# xen_matrix_controls_6x6.net
KiCad netlist of a schematic drawn in EAGLE
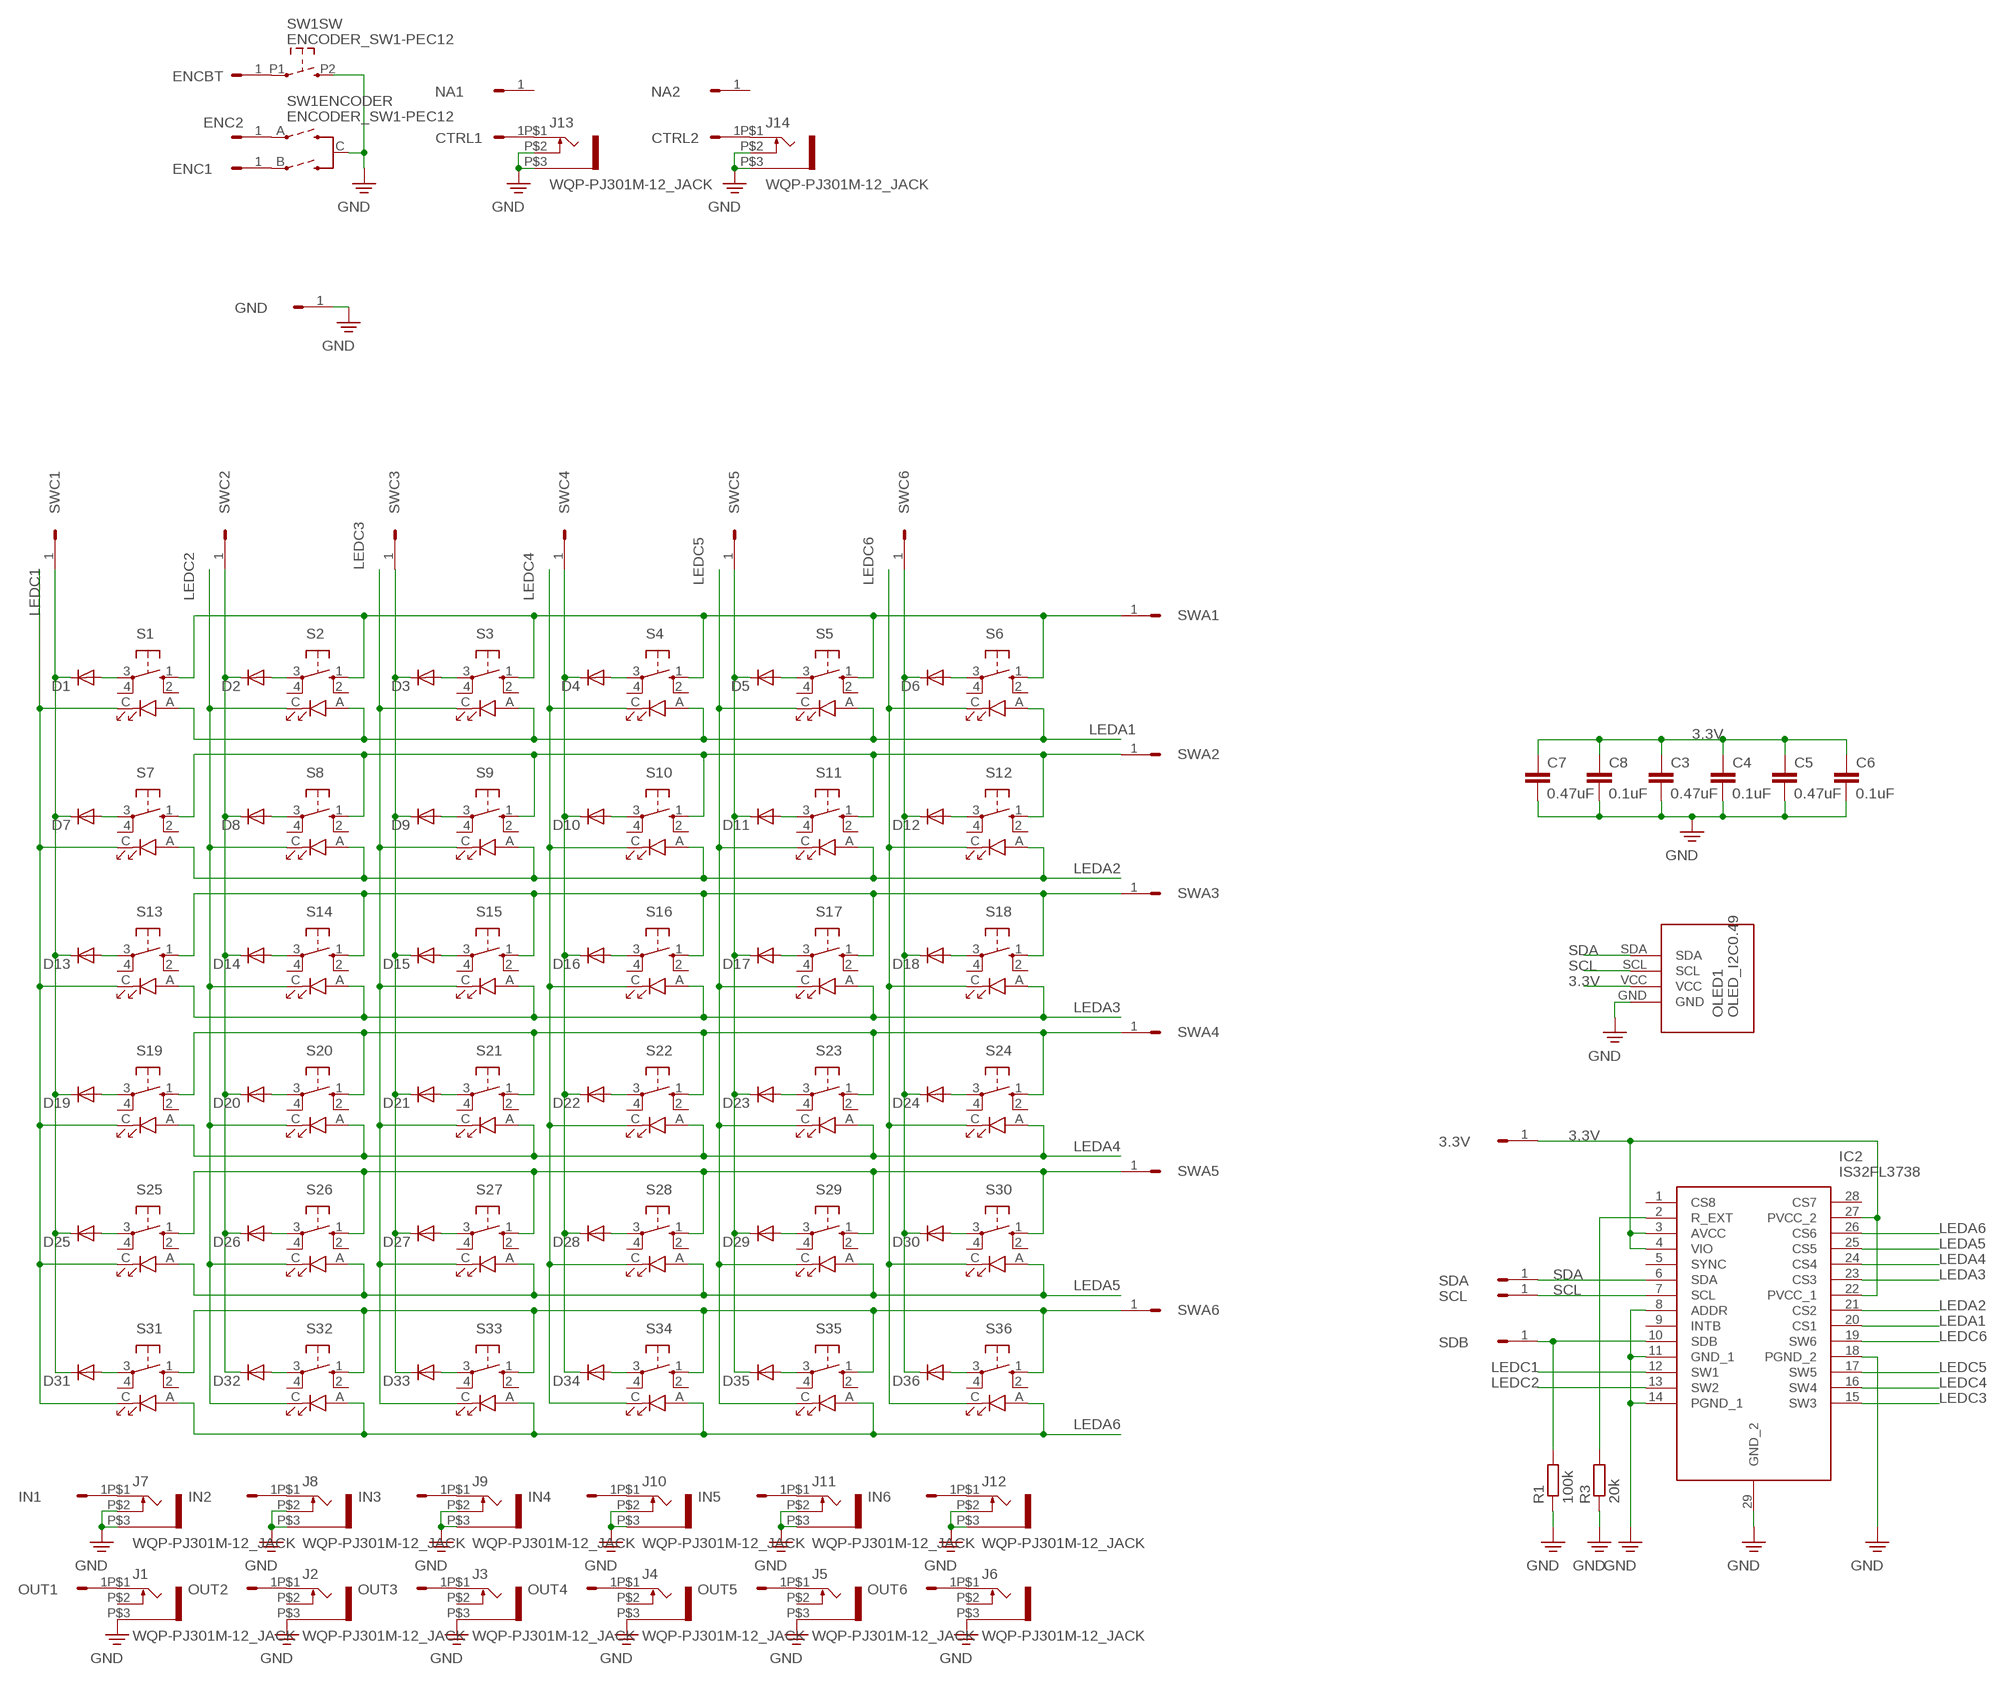
[diagram p0: schematic, sheet 1]

(export (version "E")
  (design (tool "Eeschema 10.0.6"))
  (components
    (comp (ref "3.3V")
      (value "HEADER/MALE/01")
      (footprint "eagle-import:HEADER_MALE_01")
      (fields (field (name "SPICEPREFIX") "X"))
      (libsource (lib "eagle-import") (part "HEADER/MALE/01"))
    )
    (comp (ref "C3")
      (value "0.47uF")
      (footprint "eagle-import:C0603")
      (libsource (lib "eagle-import") (part "CAPACITORC0603"))
    )
    (comp (ref "C4")
      (value "0.1uF")
      (footprint "eagle-import:C0603")
      (libsource (lib "eagle-import") (part "CAPACITORC0603"))
    )
    (comp (ref "C5")
      (value "0.47uF")
      (footprint "eagle-import:C0603")
      (libsource (lib "eagle-import") (part "CAPACITORC0603"))
    )
    (comp (ref "C6")
      (value "0.1uF")
      (footprint "eagle-import:C0603")
      (libsource (lib "eagle-import") (part "CAPACITORC0603"))
    )
    (comp (ref "C7")
      (value "0.47uF")
      (footprint "eagle-import:C0603")
      (libsource (lib "eagle-import") (part "CAPACITORC0603"))
    )
    (comp (ref "C8")
      (value "0.1uF")
      (footprint "eagle-import:C0603")
      (libsource (lib "eagle-import") (part "CAPACITORC0603"))
    )
    (comp (ref "CTRL1")
      (value "HEADER/MALE/01")
      (footprint "eagle-import:HEADER_MALE_01")
      (fields (field (name "SPICEPREFIX") "X"))
      (libsource (lib "eagle-import") (part "HEADER/MALE/01"))
    )
    (comp (ref "CTRL2")
      (value "HEADER/MALE/01")
      (footprint "eagle-import:HEADER_MALE_01")
      (fields (field (name "SPICEPREFIX") "X"))
      (libsource (lib "eagle-import") (part "HEADER/MALE/01"))
    )
    (comp (ref "D1")
      (value "1N4148SOD-123")
      (footprint "eagle-import:SOD-123")
      (libsource (lib "eagle-import") (part "1N4148SOD-123"))
    )
    (comp (ref "D2")
      (value "1N4148SOD-123")
      (footprint "eagle-import:SOD-123")
      (libsource (lib "eagle-import") (part "1N4148SOD-123"))
    )
    (comp (ref "D3")
      (value "1N4148SOD-123")
      (footprint "eagle-import:SOD-123")
      (libsource (lib "eagle-import") (part "1N4148SOD-123"))
    )
    (comp (ref "D4")
      (value "1N4148SOD-123")
      (footprint "eagle-import:SOD-123")
      (libsource (lib "eagle-import") (part "1N4148SOD-123"))
    )
    (comp (ref "D5")
      (value "1N4148SOD-123")
      (footprint "eagle-import:SOD-123")
      (libsource (lib "eagle-import") (part "1N4148SOD-123"))
    )
    (comp (ref "D6")
      (value "1N4148SOD-123")
      (footprint "eagle-import:SOD-123")
      (libsource (lib "eagle-import") (part "1N4148SOD-123"))
    )
    (comp (ref "D7")
      (value "1N4148SOD-123")
      (footprint "eagle-import:SOD-123")
      (libsource (lib "eagle-import") (part "1N4148SOD-123"))
    )
    (comp (ref "D8")
      (value "1N4148SOD-123")
      (footprint "eagle-import:SOD-123")
      (libsource (lib "eagle-import") (part "1N4148SOD-123"))
    )
    (comp (ref "D9")
      (value "1N4148SOD-123")
      (footprint "eagle-import:SOD-123")
      (libsource (lib "eagle-import") (part "1N4148SOD-123"))
    )
    (comp (ref "D10")
      (value "1N4148SOD-123")
      (footprint "eagle-import:SOD-123")
      (libsource (lib "eagle-import") (part "1N4148SOD-123"))
    )
    (comp (ref "D11")
      (value "1N4148SOD-123")
      (footprint "eagle-import:SOD-123")
      (libsource (lib "eagle-import") (part "1N4148SOD-123"))
    )
    (comp (ref "D12")
      (value "1N4148SOD-123")
      (footprint "eagle-import:SOD-123")
      (libsource (lib "eagle-import") (part "1N4148SOD-123"))
    )
    (comp (ref "D13")
      (value "1N4148SOD-123")
      (footprint "eagle-import:SOD-123")
      (libsource (lib "eagle-import") (part "1N4148SOD-123"))
    )
    (comp (ref "D14")
      (value "1N4148SOD-123")
      (footprint "eagle-import:SOD-123")
      (libsource (lib "eagle-import") (part "1N4148SOD-123"))
    )
    (comp (ref "D15")
      (value "1N4148SOD-123")
      (footprint "eagle-import:SOD-123")
      (libsource (lib "eagle-import") (part "1N4148SOD-123"))
    )
    (comp (ref "D16")
      (value "1N4148SOD-123")
      (footprint "eagle-import:SOD-123")
      (libsource (lib "eagle-import") (part "1N4148SOD-123"))
    )
    (comp (ref "D17")
      (value "1N4148SOD-123")
      (footprint "eagle-import:SOD-123")
      (libsource (lib "eagle-import") (part "1N4148SOD-123"))
    )
    (comp (ref "D18")
      (value "1N4148SOD-123")
      (footprint "eagle-import:SOD-123")
      (libsource (lib "eagle-import") (part "1N4148SOD-123"))
    )
    (comp (ref "D19")
      (value "1N4148SOD-123")
      (footprint "eagle-import:SOD-123")
      (libsource (lib "eagle-import") (part "1N4148SOD-123"))
    )
    (comp (ref "D20")
      (value "1N4148SOD-123")
      (footprint "eagle-import:SOD-123")
      (libsource (lib "eagle-import") (part "1N4148SOD-123"))
    )
    (comp (ref "D21")
      (value "1N4148SOD-123")
      (footprint "eagle-import:SOD-123")
      (libsource (lib "eagle-import") (part "1N4148SOD-123"))
    )
    (comp (ref "D22")
      (value "1N4148SOD-123")
      (footprint "eagle-import:SOD-123")
      (libsource (lib "eagle-import") (part "1N4148SOD-123"))
    )
    (comp (ref "D23")
      (value "1N4148SOD-123")
      (footprint "eagle-import:SOD-123")
      (libsource (lib "eagle-import") (part "1N4148SOD-123"))
    )
    (comp (ref "D24")
      (value "1N4148SOD-123")
      (footprint "eagle-import:SOD-123")
      (libsource (lib "eagle-import") (part "1N4148SOD-123"))
    )
    (comp (ref "D25")
      (value "1N4148SOD-123")
      (footprint "eagle-import:SOD-123")
      (libsource (lib "eagle-import") (part "1N4148SOD-123"))
    )
    (comp (ref "D26")
      (value "1N4148SOD-123")
      (footprint "eagle-import:SOD-123")
      (libsource (lib "eagle-import") (part "1N4148SOD-123"))
    )
    (comp (ref "D27")
      (value "1N4148SOD-123")
      (footprint "eagle-import:SOD-123")
      (libsource (lib "eagle-import") (part "1N4148SOD-123"))
    )
    (comp (ref "D28")
      (value "1N4148SOD-123")
      (footprint "eagle-import:SOD-123")
      (libsource (lib "eagle-import") (part "1N4148SOD-123"))
    )
    (comp (ref "D29")
      (value "1N4148SOD-123")
      (footprint "eagle-import:SOD-123")
      (libsource (lib "eagle-import") (part "1N4148SOD-123"))
    )
    (comp (ref "D30")
      (value "1N4148SOD-123")
      (footprint "eagle-import:SOD-123")
      (libsource (lib "eagle-import") (part "1N4148SOD-123"))
    )
    (comp (ref "D31")
      (value "1N4148SOD-123")
      (footprint "eagle-import:SOD-123")
      (libsource (lib "eagle-import") (part "1N4148SOD-123"))
    )
    (comp (ref "D32")
      (value "1N4148SOD-123")
      (footprint "eagle-import:SOD-123")
      (libsource (lib "eagle-import") (part "1N4148SOD-123"))
    )
    (comp (ref "D33")
      (value "1N4148SOD-123")
      (footprint "eagle-import:SOD-123")
      (libsource (lib "eagle-import") (part "1N4148SOD-123"))
    )
    (comp (ref "D34")
      (value "1N4148SOD-123")
      (footprint "eagle-import:SOD-123")
      (libsource (lib "eagle-import") (part "1N4148SOD-123"))
    )
    (comp (ref "D35")
      (value "1N4148SOD-123")
      (footprint "eagle-import:SOD-123")
      (libsource (lib "eagle-import") (part "1N4148SOD-123"))
    )
    (comp (ref "D36")
      (value "1N4148SOD-123")
      (footprint "eagle-import:SOD-123")
      (libsource (lib "eagle-import") (part "1N4148SOD-123"))
    )
    (comp (ref "ENC1")
      (value "HEADER/MALE/01")
      (footprint "eagle-import:HEADER_MALE_01")
      (fields (field (name "SPICEPREFIX") "X"))
      (libsource (lib "eagle-import") (part "HEADER/MALE/01"))
    )
    (comp (ref "ENC2")
      (value "HEADER/MALE/01")
      (footprint "eagle-import:HEADER_MALE_01")
      (fields (field (name "SPICEPREFIX") "X"))
      (libsource (lib "eagle-import") (part "HEADER/MALE/01"))
    )
    (comp (ref "ENCBT")
      (value "HEADER/MALE/01")
      (footprint "eagle-import:HEADER_MALE_01")
      (fields (field (name "SPICEPREFIX") "X"))
      (libsource (lib "eagle-import") (part "HEADER/MALE/01"))
    )
    (comp (ref "GND")
      (value "HEADER/MALE/01")
      (footprint "eagle-import:HEADER_MALE_01")
      (fields (field (name "SPICEPREFIX") "X"))
      (libsource (lib "eagle-import") (part "HEADER/MALE/01"))
    )
    (comp (ref "IC2")
      (value "IS32FL3738")
      (footprint "eagle-import:TSSOP29")
      (fields (field (name "MANUFACTURER_PART_NUMBER") "IS32FL3738-ZLA3-TR"))
      (libsource (lib "eagle-import") (part "IS32FL3738"))
    )
    (comp (ref "IN1")
      (value "HEADER/MALE/01")
      (footprint "eagle-import:HEADER_MALE_01")
      (fields (field (name "SPICEPREFIX") "X"))
      (libsource (lib "eagle-import") (part "HEADER/MALE/01"))
    )
    (comp (ref "IN2")
      (value "HEADER/MALE/01")
      (footprint "eagle-import:HEADER_MALE_01")
      (fields (field (name "SPICEPREFIX") "X"))
      (libsource (lib "eagle-import") (part "HEADER/MALE/01"))
    )
    (comp (ref "IN3")
      (value "HEADER/MALE/01")
      (footprint "eagle-import:HEADER_MALE_01")
      (fields (field (name "SPICEPREFIX") "X"))
      (libsource (lib "eagle-import") (part "HEADER/MALE/01"))
    )
    (comp (ref "IN4")
      (value "HEADER/MALE/01")
      (footprint "eagle-import:HEADER_MALE_01")
      (fields (field (name "SPICEPREFIX") "X"))
      (libsource (lib "eagle-import") (part "HEADER/MALE/01"))
    )
    (comp (ref "IN5")
      (value "HEADER/MALE/01")
      (footprint "eagle-import:HEADER_MALE_01")
      (fields (field (name "SPICEPREFIX") "X"))
      (libsource (lib "eagle-import") (part "HEADER/MALE/01"))
    )
    (comp (ref "IN6")
      (value "HEADER/MALE/01")
      (footprint "eagle-import:HEADER_MALE_01")
      (fields (field (name "SPICEPREFIX") "X"))
      (libsource (lib "eagle-import") (part "HEADER/MALE/01"))
    )
    (comp (ref "J1")
      (value "WQP-PJ301M-12_JACK")
      (footprint "eagle-import:WQP-PJ301M-12_JACK")
      (libsource (lib "eagle-import") (part "WQP-PJ301M-12_JACK"))
    )
    (comp (ref "J2")
      (value "WQP-PJ301M-12_JACK")
      (footprint "eagle-import:WQP-PJ301M-12_JACK")
      (libsource (lib "eagle-import") (part "WQP-PJ301M-12_JACK"))
    )
    (comp (ref "J3")
      (value "WQP-PJ301M-12_JACK")
      (footprint "eagle-import:WQP-PJ301M-12_JACK")
      (libsource (lib "eagle-import") (part "WQP-PJ301M-12_JACK"))
    )
    (comp (ref "J4")
      (value "WQP-PJ301M-12_JACK")
      (footprint "eagle-import:WQP-PJ301M-12_JACK")
      (libsource (lib "eagle-import") (part "WQP-PJ301M-12_JACK"))
    )
    (comp (ref "J5")
      (value "WQP-PJ301M-12_JACK")
      (footprint "eagle-import:WQP-PJ301M-12_JACK")
      (libsource (lib "eagle-import") (part "WQP-PJ301M-12_JACK"))
    )
    (comp (ref "J6")
      (value "WQP-PJ301M-12_JACK")
      (footprint "eagle-import:WQP-PJ301M-12_JACK")
      (libsource (lib "eagle-import") (part "WQP-PJ301M-12_JACK"))
    )
    (comp (ref "J7")
      (value "WQP-PJ301M-12_JACK")
      (footprint "eagle-import:WQP-PJ301M-12_JACK")
      (libsource (lib "eagle-import") (part "WQP-PJ301M-12_JACK"))
    )
    (comp (ref "J8")
      (value "WQP-PJ301M-12_JACK")
      (footprint "eagle-import:WQP-PJ301M-12_JACK")
      (libsource (lib "eagle-import") (part "WQP-PJ301M-12_JACK"))
    )
    (comp (ref "J9")
      (value "WQP-PJ301M-12_JACK")
      (footprint "eagle-import:WQP-PJ301M-12_JACK")
      (libsource (lib "eagle-import") (part "WQP-PJ301M-12_JACK"))
    )
    (comp (ref "J10")
      (value "WQP-PJ301M-12_JACK")
      (footprint "eagle-import:WQP-PJ301M-12_JACK")
      (libsource (lib "eagle-import") (part "WQP-PJ301M-12_JACK"))
    )
    (comp (ref "J11")
      (value "WQP-PJ301M-12_JACK")
      (footprint "eagle-import:WQP-PJ301M-12_JACK")
      (libsource (lib "eagle-import") (part "WQP-PJ301M-12_JACK"))
    )
    (comp (ref "J12")
      (value "WQP-PJ301M-12_JACK")
      (footprint "eagle-import:WQP-PJ301M-12_JACK")
      (libsource (lib "eagle-import") (part "WQP-PJ301M-12_JACK"))
    )
    (comp (ref "J13")
      (value "WQP-PJ301M-12_JACK")
      (footprint "eagle-import:WQP-PJ301M-12_JACK")
      (libsource (lib "eagle-import") (part "WQP-PJ301M-12_JACK"))
    )
    (comp (ref "J14")
      (value "WQP-PJ301M-12_JACK")
      (footprint "eagle-import:WQP-PJ301M-12_JACK")
      (libsource (lib "eagle-import") (part "WQP-PJ301M-12_JACK"))
    )
    (comp (ref "NA1")
      (value "HEADER/MALE/01")
      (footprint "eagle-import:HEADER_MALE_01")
      (fields (field (name "SPICEPREFIX") "X"))
      (libsource (lib "eagle-import") (part "HEADER/MALE/01"))
    )
    (comp (ref "NA2")
      (value "HEADER/MALE/01")
      (footprint "eagle-import:HEADER_MALE_01")
      (fields (field (name "SPICEPREFIX") "X"))
      (libsource (lib "eagle-import") (part "HEADER/MALE/01"))
    )
    (comp (ref "OLED1")
      (value "OLED_I2C0.49")
      (footprint "eagle-import:OLEDM0.49")
      (libsource (lib "eagle-import") (part "OLED_I2C0.49"))
    )
    (comp (ref "OUT1")
      (value "HEADER/MALE/01")
      (footprint "eagle-import:HEADER_MALE_01")
      (fields (field (name "SPICEPREFIX") "X"))
      (libsource (lib "eagle-import") (part "HEADER/MALE/01"))
    )
    (comp (ref "OUT2")
      (value "HEADER/MALE/01")
      (footprint "eagle-import:HEADER_MALE_01")
      (fields (field (name "SPICEPREFIX") "X"))
      (libsource (lib "eagle-import") (part "HEADER/MALE/01"))
    )
    (comp (ref "OUT3")
      (value "HEADER/MALE/01")
      (footprint "eagle-import:HEADER_MALE_01")
      (fields (field (name "SPICEPREFIX") "X"))
      (libsource (lib "eagle-import") (part "HEADER/MALE/01"))
    )
    (comp (ref "OUT4")
      (value "HEADER/MALE/01")
      (footprint "eagle-import:HEADER_MALE_01")
      (fields (field (name "SPICEPREFIX") "X"))
      (libsource (lib "eagle-import") (part "HEADER/MALE/01"))
    )
    (comp (ref "OUT5")
      (value "HEADER/MALE/01")
      (footprint "eagle-import:HEADER_MALE_01")
      (fields (field (name "SPICEPREFIX") "X"))
      (libsource (lib "eagle-import") (part "HEADER/MALE/01"))
    )
    (comp (ref "OUT6")
      (value "HEADER/MALE/01")
      (footprint "eagle-import:HEADER_MALE_01")
      (fields (field (name "SPICEPREFIX") "X"))
      (libsource (lib "eagle-import") (part "HEADER/MALE/01"))
    )
    (comp (ref "R1")
      (value "100k")
      (footprint "eagle-import:R0603")
      (libsource (lib "eagle-import") (part "RESISTOR"))
    )
    (comp (ref "R3")
      (value "20k")
      (footprint "eagle-import:R0603")
      (libsource (lib "eagle-import") (part "RESISTOR"))
    )
    (comp (ref "S1")
      (value "SW-LEDTHONK")
      (footprint "eagle-import:SW-PUSH-TACT-LED-THONK")
      (libsource (lib "eagle-import") (part "SW-LEDTHONK"))
    )
    (comp (ref "S2")
      (value "SW-LEDTHONK")
      (footprint "eagle-import:SW-PUSH-TACT-LED-THONK")
      (libsource (lib "eagle-import") (part "SW-LEDTHONK"))
    )
    (comp (ref "S3")
      (value "SW-LEDTHONK")
      (footprint "eagle-import:SW-PUSH-TACT-LED-THONK")
      (libsource (lib "eagle-import") (part "SW-LEDTHONK"))
    )
    (comp (ref "S4")
      (value "SW-LEDTHONK")
      (footprint "eagle-import:SW-PUSH-TACT-LED-THONK")
      (libsource (lib "eagle-import") (part "SW-LEDTHONK"))
    )
    (comp (ref "S5")
      (value "SW-LEDTHONK")
      (footprint "eagle-import:SW-PUSH-TACT-LED-THONK")
      (libsource (lib "eagle-import") (part "SW-LEDTHONK"))
    )
    (comp (ref "S6")
      (value "SW-LEDTHONK")
      (footprint "eagle-import:SW-PUSH-TACT-LED-THONK")
      (libsource (lib "eagle-import") (part "SW-LEDTHONK"))
    )
    (comp (ref "S7")
      (value "SW-LEDTHONK")
      (footprint "eagle-import:SW-PUSH-TACT-LED-THONK")
      (libsource (lib "eagle-import") (part "SW-LEDTHONK"))
    )
    (comp (ref "S8")
      (value "SW-LEDTHONK")
      (footprint "eagle-import:SW-PUSH-TACT-LED-THONK")
      (libsource (lib "eagle-import") (part "SW-LEDTHONK"))
    )
    (comp (ref "S9")
      (value "SW-LEDTHONK")
      (footprint "eagle-import:SW-PUSH-TACT-LED-THONK")
      (libsource (lib "eagle-import") (part "SW-LEDTHONK"))
    )
    (comp (ref "S10")
      (value "SW-LEDTHONK")
      (footprint "eagle-import:SW-PUSH-TACT-LED-THONK")
      (libsource (lib "eagle-import") (part "SW-LEDTHONK"))
    )
    (comp (ref "S11")
      (value "SW-LEDTHONK")
      (footprint "eagle-import:SW-PUSH-TACT-LED-THONK")
      (libsource (lib "eagle-import") (part "SW-LEDTHONK"))
    )
    (comp (ref "S12")
      (value "SW-LEDTHONK")
      (footprint "eagle-import:SW-PUSH-TACT-LED-THONK")
      (libsource (lib "eagle-import") (part "SW-LEDTHONK"))
    )
    (comp (ref "S13")
      (value "SW-LEDTHONK")
      (footprint "eagle-import:SW-PUSH-TACT-LED-THONK")
      (libsource (lib "eagle-import") (part "SW-LEDTHONK"))
    )
    (comp (ref "S14")
      (value "SW-LEDTHONK")
      (footprint "eagle-import:SW-PUSH-TACT-LED-THONK")
      (libsource (lib "eagle-import") (part "SW-LEDTHONK"))
    )
    (comp (ref "S15")
      (value "SW-LEDTHONK")
      (footprint "eagle-import:SW-PUSH-TACT-LED-THONK")
      (libsource (lib "eagle-import") (part "SW-LEDTHONK"))
    )
    (comp (ref "S16")
      (value "SW-LEDTHONK")
      (footprint "eagle-import:SW-PUSH-TACT-LED-THONK")
      (libsource (lib "eagle-import") (part "SW-LEDTHONK"))
    )
    (comp (ref "S17")
      (value "SW-LEDTHONK")
      (footprint "eagle-import:SW-PUSH-TACT-LED-THONK")
      (libsource (lib "eagle-import") (part "SW-LEDTHONK"))
    )
    (comp (ref "S18")
      (value "SW-LEDTHONK")
      (footprint "eagle-import:SW-PUSH-TACT-LED-THONK")
      (libsource (lib "eagle-import") (part "SW-LEDTHONK"))
    )
    (comp (ref "S19")
      (value "SW-LEDTHONK")
      (footprint "eagle-import:SW-PUSH-TACT-LED-THONK")
      (libsource (lib "eagle-import") (part "SW-LEDTHONK"))
    )
    (comp (ref "S20")
      (value "SW-LEDTHONK")
      (footprint "eagle-import:SW-PUSH-TACT-LED-THONK")
      (libsource (lib "eagle-import") (part "SW-LEDTHONK"))
    )
    (comp (ref "S21")
      (value "SW-LEDTHONK")
      (footprint "eagle-import:SW-PUSH-TACT-LED-THONK")
      (libsource (lib "eagle-import") (part "SW-LEDTHONK"))
    )
    (comp (ref "S22")
      (value "SW-LEDTHONK")
      (footprint "eagle-import:SW-PUSH-TACT-LED-THONK")
      (libsource (lib "eagle-import") (part "SW-LEDTHONK"))
    )
    (comp (ref "S23")
      (value "SW-LEDTHONK")
      (footprint "eagle-import:SW-PUSH-TACT-LED-THONK")
      (libsource (lib "eagle-import") (part "SW-LEDTHONK"))
    )
    (comp (ref "S24")
      (value "SW-LEDTHONK")
      (footprint "eagle-import:SW-PUSH-TACT-LED-THONK")
      (libsource (lib "eagle-import") (part "SW-LEDTHONK"))
    )
    (comp (ref "S25")
      (value "SW-LEDTHONK")
      (footprint "eagle-import:SW-PUSH-TACT-LED-THONK")
      (libsource (lib "eagle-import") (part "SW-LEDTHONK"))
    )
    (comp (ref "S26")
      (value "SW-LEDTHONK")
      (footprint "eagle-import:SW-PUSH-TACT-LED-THONK")
      (libsource (lib "eagle-import") (part "SW-LEDTHONK"))
    )
    (comp (ref "S27")
      (value "SW-LEDTHONK")
      (footprint "eagle-import:SW-PUSH-TACT-LED-THONK")
      (libsource (lib "eagle-import") (part "SW-LEDTHONK"))
    )
    (comp (ref "S28")
      (value "SW-LEDTHONK")
      (footprint "eagle-import:SW-PUSH-TACT-LED-THONK")
      (libsource (lib "eagle-import") (part "SW-LEDTHONK"))
    )
    (comp (ref "S29")
      (value "SW-LEDTHONK")
      (footprint "eagle-import:SW-PUSH-TACT-LED-THONK")
      (libsource (lib "eagle-import") (part "SW-LEDTHONK"))
    )
    (comp (ref "S30")
      (value "SW-LEDTHONK")
      (footprint "eagle-import:SW-PUSH-TACT-LED-THONK")
      (libsource (lib "eagle-import") (part "SW-LEDTHONK"))
    )
    (comp (ref "S31")
      (value "SW-LEDTHONK")
      (footprint "eagle-import:SW-PUSH-TACT-LED-THONK")
      (libsource (lib "eagle-import") (part "SW-LEDTHONK"))
    )
    (comp (ref "S32")
      (value "SW-LEDTHONK")
      (footprint "eagle-import:SW-PUSH-TACT-LED-THONK")
      (libsource (lib "eagle-import") (part "SW-LEDTHONK"))
    )
    (comp (ref "S33")
      (value "SW-LEDTHONK")
      (footprint "eagle-import:SW-PUSH-TACT-LED-THONK")
      (libsource (lib "eagle-import") (part "SW-LEDTHONK"))
    )
    (comp (ref "S34")
      (value "SW-LEDTHONK")
      (footprint "eagle-import:SW-PUSH-TACT-LED-THONK")
      (libsource (lib "eagle-import") (part "SW-LEDTHONK"))
    )
    (comp (ref "S35")
      (value "SW-LEDTHONK")
      (footprint "eagle-import:SW-PUSH-TACT-LED-THONK")
      (libsource (lib "eagle-import") (part "SW-LEDTHONK"))
    )
    (comp (ref "S36")
      (value "SW-LEDTHONK")
      (footprint "eagle-import:SW-PUSH-TACT-LED-THONK")
      (libsource (lib "eagle-import") (part "SW-LEDTHONK"))
    )
    (comp (ref "SCL")
      (value "HEADER/MALE/01")
      (footprint "eagle-import:HEADER_MALE_01")
      (fields (field (name "SPICEPREFIX") "X"))
      (libsource (lib "eagle-import") (part "HEADER/MALE/01"))
    )
    (comp (ref "SDA")
      (value "HEADER/MALE/01")
      (footprint "eagle-import:HEADER_MALE_01")
      (fields (field (name "SPICEPREFIX") "X"))
      (libsource (lib "eagle-import") (part "HEADER/MALE/01"))
    )
    (comp (ref "SDB")
      (value "HEADER/MALE/01")
      (footprint "eagle-import:HEADER_MALE_01")
      (fields (field (name "SPICEPREFIX") "X"))
      (libsource (lib "eagle-import") (part "HEADER/MALE/01"))
    )
    (comp (ref "SW1")
      (value "ENCODER_SW1-PEC12")
      (footprint "eagle-import:PEC12_INCREMENTAL_ENCODER")
      (libsource (lib "eagle-import") (part "ENCODER_SW1-PEC12"))
    )
    (comp (ref "SWA1")
      (value "HEADER/MALE/01")
      (footprint "eagle-import:HEADER_MALE_01")
      (fields (field (name "SPICEPREFIX") "X"))
      (libsource (lib "eagle-import") (part "HEADER/MALE/01"))
    )
    (comp (ref "SWA2")
      (value "HEADER/MALE/01")
      (footprint "eagle-import:HEADER_MALE_01")
      (fields (field (name "SPICEPREFIX") "X"))
      (libsource (lib "eagle-import") (part "HEADER/MALE/01"))
    )
    (comp (ref "SWA3")
      (value "HEADER/MALE/01")
      (footprint "eagle-import:HEADER_MALE_01")
      (fields (field (name "SPICEPREFIX") "X"))
      (libsource (lib "eagle-import") (part "HEADER/MALE/01"))
    )
    (comp (ref "SWA4")
      (value "HEADER/MALE/01")
      (footprint "eagle-import:HEADER_MALE_01")
      (fields (field (name "SPICEPREFIX") "X"))
      (libsource (lib "eagle-import") (part "HEADER/MALE/01"))
    )
    (comp (ref "SWA5")
      (value "HEADER/MALE/01")
      (footprint "eagle-import:HEADER_MALE_01")
      (fields (field (name "SPICEPREFIX") "X"))
      (libsource (lib "eagle-import") (part "HEADER/MALE/01"))
    )
    (comp (ref "SWA6")
      (value "HEADER/MALE/01")
      (footprint "eagle-import:HEADER_MALE_01")
      (fields (field (name "SPICEPREFIX") "X"))
      (libsource (lib "eagle-import") (part "HEADER/MALE/01"))
    )
    (comp (ref "SWC1")
      (value "HEADER/MALE/01")
      (footprint "eagle-import:HEADER_MALE_01")
      (fields (field (name "SPICEPREFIX") "X"))
      (libsource (lib "eagle-import") (part "HEADER/MALE/01"))
    )
    (comp (ref "SWC2")
      (value "HEADER/MALE/01")
      (footprint "eagle-import:HEADER_MALE_01")
      (fields (field (name "SPICEPREFIX") "X"))
      (libsource (lib "eagle-import") (part "HEADER/MALE/01"))
    )
    (comp (ref "SWC3")
      (value "HEADER/MALE/01")
      (footprint "eagle-import:HEADER_MALE_01")
      (fields (field (name "SPICEPREFIX") "X"))
      (libsource (lib "eagle-import") (part "HEADER/MALE/01"))
    )
    (comp (ref "SWC4")
      (value "HEADER/MALE/01")
      (footprint "eagle-import:HEADER_MALE_01")
      (fields (field (name "SPICEPREFIX") "X"))
      (libsource (lib "eagle-import") (part "HEADER/MALE/01"))
    )
    (comp (ref "SWC5")
      (value "HEADER/MALE/01")
      (footprint "eagle-import:HEADER_MALE_01")
      (fields (field (name "SPICEPREFIX") "X"))
      (libsource (lib "eagle-import") (part "HEADER/MALE/01"))
    )
    (comp (ref "SWC6")
      (value "HEADER/MALE/01")
      (footprint "eagle-import:HEADER_MALE_01")
      (fields (field (name "SPICEPREFIX") "X"))
      (libsource (lib "eagle-import") (part "HEADER/MALE/01"))
    )
  )
  (nets
    (net (code "1") (name "/3.3V") (class "Default")
      (node (ref "3.3V") (pin "1") (pinfunction "3_1") (pintype "passive"))
      (node (ref "C3") (pin "1") (pinfunction "1_1") (pintype "passive"))
      (node (ref "C4") (pin "1") (pinfunction "1_1") (pintype "passive"))
      (node (ref "C5") (pin "1") (pinfunction "1_1") (pintype "passive"))
      (node (ref "C6") (pin "1") (pinfunction "1_1") (pintype "passive"))
      (node (ref "C7") (pin "1") (pinfunction "1_1") (pintype "passive"))
      (node (ref "C8") (pin "1") (pinfunction "1_1") (pintype "passive"))
      (node (ref "IC2") (pin "22") (pinfunction "PVCC_1_22") (pintype "power_in"))
      (node (ref "IC2") (pin "27") (pinfunction "PVCC_2_27") (pintype "power_in"))
      (node (ref "IC2") (pin "3") (pinfunction "AVCC_3") (pintype "power_in"))
      (node (ref "IC2") (pin "4") (pinfunction "VIO_4") (pintype "input"))
      (node (ref "OLED1") (pin "VCC") (pinfunction "VCC_VCC") (pintype "bidirectional"))
    )
    (net (code "2") (name "/LEDA1") (class "Default")
      (node (ref "IC2") (pin "20") (pinfunction "CS1_20") (pintype "output"))
      (node (ref "S1") (pin "A") (pinfunction "A_A") (pintype "passive"))
      (node (ref "S2") (pin "A") (pinfunction "A_A") (pintype "passive"))
      (node (ref "S3") (pin "A") (pinfunction "A_A") (pintype "passive"))
      (node (ref "S4") (pin "A") (pinfunction "A_A") (pintype "passive"))
      (node (ref "S5") (pin "A") (pinfunction "A_A") (pintype "passive"))
      (node (ref "S6") (pin "A") (pinfunction "A_A") (pintype "passive"))
    )
    (net (code "3") (name "/LEDA2") (class "Default")
      (node (ref "IC2") (pin "21") (pinfunction "CS2_21") (pintype "output"))
      (node (ref "S10") (pin "A") (pinfunction "A_A") (pintype "passive"))
      (node (ref "S11") (pin "A") (pinfunction "A_A") (pintype "passive"))
      (node (ref "S12") (pin "A") (pinfunction "A_A") (pintype "passive"))
      (node (ref "S7") (pin "A") (pinfunction "A_A") (pintype "passive"))
      (node (ref "S8") (pin "A") (pinfunction "A_A") (pintype "passive"))
      (node (ref "S9") (pin "A") (pinfunction "A_A") (pintype "passive"))
    )
    (net (code "4") (name "/LEDA3") (class "Default")
      (node (ref "IC2") (pin "23") (pinfunction "CS3_23") (pintype "bidirectional"))
      (node (ref "S13") (pin "A") (pinfunction "A_A") (pintype "passive"))
      (node (ref "S14") (pin "A") (pinfunction "A_A") (pintype "passive"))
      (node (ref "S15") (pin "A") (pinfunction "A_A") (pintype "passive"))
      (node (ref "S16") (pin "A") (pinfunction "A_A") (pintype "passive"))
      (node (ref "S17") (pin "A") (pinfunction "A_A") (pintype "passive"))
      (node (ref "S18") (pin "A") (pinfunction "A_A") (pintype "passive"))
    )
    (net (code "5") (name "/LEDA4") (class "Default")
      (node (ref "IC2") (pin "24") (pinfunction "CS4_24") (pintype "bidirectional"))
      (node (ref "S19") (pin "A") (pinfunction "A_A") (pintype "passive"))
      (node (ref "S20") (pin "A") (pinfunction "A_A") (pintype "passive"))
      (node (ref "S21") (pin "A") (pinfunction "A_A") (pintype "passive"))
      (node (ref "S22") (pin "A") (pinfunction "A_A") (pintype "passive"))
      (node (ref "S23") (pin "A") (pinfunction "A_A") (pintype "passive"))
      (node (ref "S24") (pin "A") (pinfunction "A_A") (pintype "passive"))
    )
    (net (code "6") (name "/LEDA5") (class "Default")
      (node (ref "IC2") (pin "25") (pinfunction "CS5_25") (pintype "bidirectional"))
      (node (ref "S25") (pin "A") (pinfunction "A_A") (pintype "passive"))
      (node (ref "S26") (pin "A") (pinfunction "A_A") (pintype "passive"))
      (node (ref "S27") (pin "A") (pinfunction "A_A") (pintype "passive"))
      (node (ref "S28") (pin "A") (pinfunction "A_A") (pintype "passive"))
      (node (ref "S29") (pin "A") (pinfunction "A_A") (pintype "passive"))
      (node (ref "S30") (pin "A") (pinfunction "A_A") (pintype "passive"))
    )
    (net (code "7") (name "/LEDA6") (class "Default")
      (node (ref "IC2") (pin "26") (pinfunction "CS6_26") (pintype "bidirectional"))
      (node (ref "S31") (pin "A") (pinfunction "A_A") (pintype "passive"))
      (node (ref "S32") (pin "A") (pinfunction "A_A") (pintype "passive"))
      (node (ref "S33") (pin "A") (pinfunction "A_A") (pintype "passive"))
      (node (ref "S34") (pin "A") (pinfunction "A_A") (pintype "passive"))
      (node (ref "S35") (pin "A") (pinfunction "A_A") (pintype "passive"))
      (node (ref "S36") (pin "A") (pinfunction "A_A") (pintype "passive"))
    )
    (net (code "8") (name "/LEDC1") (class "Default")
      (node (ref "IC2") (pin "12") (pinfunction "SW1_12") (pintype "output"))
      (node (ref "S1") (pin "C") (pinfunction "C_C") (pintype "passive"))
      (node (ref "S13") (pin "C") (pinfunction "C_C") (pintype "passive"))
      (node (ref "S19") (pin "C") (pinfunction "C_C") (pintype "passive"))
      (node (ref "S25") (pin "C") (pinfunction "C_C") (pintype "passive"))
      (node (ref "S31") (pin "C") (pinfunction "C_C") (pintype "passive"))
      (node (ref "S7") (pin "C") (pinfunction "C_C") (pintype "passive"))
    )
    (net (code "9") (name "/LEDC2") (class "Default")
      (node (ref "IC2") (pin "13") (pinfunction "SW2_13") (pintype "output"))
      (node (ref "S14") (pin "C") (pinfunction "C_C") (pintype "passive"))
      (node (ref "S2") (pin "C") (pinfunction "C_C") (pintype "passive"))
      (node (ref "S20") (pin "C") (pinfunction "C_C") (pintype "passive"))
      (node (ref "S26") (pin "C") (pinfunction "C_C") (pintype "passive"))
      (node (ref "S32") (pin "C") (pinfunction "C_C") (pintype "passive"))
      (node (ref "S8") (pin "C") (pinfunction "C_C") (pintype "passive"))
    )
    (net (code "10") (name "/LEDC3") (class "Default")
      (node (ref "IC2") (pin "15") (pinfunction "SW3_15") (pintype "output"))
      (node (ref "S15") (pin "C") (pinfunction "C_C") (pintype "passive"))
      (node (ref "S21") (pin "C") (pinfunction "C_C") (pintype "passive"))
      (node (ref "S27") (pin "C") (pinfunction "C_C") (pintype "passive"))
      (node (ref "S3") (pin "C") (pinfunction "C_C") (pintype "passive"))
      (node (ref "S33") (pin "C") (pinfunction "C_C") (pintype "passive"))
      (node (ref "S9") (pin "C") (pinfunction "C_C") (pintype "passive"))
    )
    (net (code "11") (name "/LEDC4") (class "Default")
      (node (ref "IC2") (pin "16") (pinfunction "SW4_16") (pintype "output"))
      (node (ref "S10") (pin "C") (pinfunction "C_C") (pintype "passive"))
      (node (ref "S16") (pin "C") (pinfunction "C_C") (pintype "passive"))
      (node (ref "S22") (pin "C") (pinfunction "C_C") (pintype "passive"))
      (node (ref "S28") (pin "C") (pinfunction "C_C") (pintype "passive"))
      (node (ref "S34") (pin "C") (pinfunction "C_C") (pintype "passive"))
      (node (ref "S4") (pin "C") (pinfunction "C_C") (pintype "passive"))
    )
    (net (code "12") (name "/LEDC5") (class "Default")
      (node (ref "IC2") (pin "17") (pinfunction "SW5_17") (pintype "output"))
      (node (ref "S11") (pin "C") (pinfunction "C_C") (pintype "passive"))
      (node (ref "S17") (pin "C") (pinfunction "C_C") (pintype "passive"))
      (node (ref "S23") (pin "C") (pinfunction "C_C") (pintype "passive"))
      (node (ref "S29") (pin "C") (pinfunction "C_C") (pintype "passive"))
      (node (ref "S35") (pin "C") (pinfunction "C_C") (pintype "passive"))
      (node (ref "S5") (pin "C") (pinfunction "C_C") (pintype "passive"))
    )
    (net (code "13") (name "/LEDC6") (class "Default")
      (node (ref "IC2") (pin "19") (pinfunction "SW6_19") (pintype "output"))
      (node (ref "S12") (pin "C") (pinfunction "C_C") (pintype "passive"))
      (node (ref "S18") (pin "C") (pinfunction "C_C") (pintype "passive"))
      (node (ref "S24") (pin "C") (pinfunction "C_C") (pintype "passive"))
      (node (ref "S30") (pin "C") (pinfunction "C_C") (pintype "passive"))
      (node (ref "S36") (pin "C") (pinfunction "C_C") (pintype "passive"))
      (node (ref "S6") (pin "C") (pinfunction "C_C") (pintype "passive"))
    )
    (net (code "14") (name "/SCL") (class "Default")
      (node (ref "IC2") (pin "7") (pinfunction "SCL_7") (pintype "bidirectional"))
      (node (ref "OLED1") (pin "SCL") (pinfunction "SCL_SCL") (pintype "bidirectional"))
      (node (ref "SCL") (pin "1") (pinfunction "3_1") (pintype "passive"))
    )
    (net (code "15") (name "/SDA") (class "Default")
      (node (ref "IC2") (pin "6") (pinfunction "SDA_6") (pintype "bidirectional"))
      (node (ref "OLED1") (pin "SDA") (pinfunction "SDA_SDA") (pintype "bidirectional"))
      (node (ref "SDA") (pin "1") (pinfunction "3_1") (pintype "passive"))
    )
    (net (code "16") (name "GND") (class "Default")
      (node (ref "C3") (pin "2") (pinfunction "2_2") (pintype "passive"))
      (node (ref "C4") (pin "2") (pinfunction "2_2") (pintype "passive"))
      (node (ref "C5") (pin "2") (pinfunction "2_2") (pintype "passive"))
      (node (ref "C6") (pin "2") (pinfunction "2_2") (pintype "passive"))
      (node (ref "C7") (pin "2") (pinfunction "2_2") (pintype "passive"))
      (node (ref "C8") (pin "2") (pinfunction "2_2") (pintype "passive"))
      (node (ref "GND") (pin "1") (pinfunction "3_1") (pintype "passive"))
      (node (ref "IC2") (pin "11") (pinfunction "GND_1_11") (pintype "power_in"))
      (node (ref "IC2") (pin "14") (pinfunction "PGND_1_14") (pintype "power_in"))
      (node (ref "IC2") (pin "18") (pinfunction "PGND_2_18") (pintype "power_in"))
      (node (ref "IC2") (pin "29") (pinfunction "GND_2_29") (pintype "power_in"))
      (node (ref "IC2") (pin "8") (pinfunction "ADDR_8") (pintype "input"))
      (node (ref "J1") (pin "P$3") (pinfunction "1_P$3") (pintype "passive"))
      (node (ref "J10") (pin "P$2") (pinfunction "3_P$2") (pintype "passive"))
      (node (ref "J10") (pin "P$3") (pinfunction "1_P$3") (pintype "passive"))
      (node (ref "J11") (pin "P$2") (pinfunction "3_P$2") (pintype "passive"))
      (node (ref "J11") (pin "P$3") (pinfunction "1_P$3") (pintype "passive"))
      (node (ref "J12") (pin "P$2") (pinfunction "3_P$2") (pintype "passive"))
      (node (ref "J12") (pin "P$3") (pinfunction "1_P$3") (pintype "passive"))
      (node (ref "J13") (pin "P$2") (pinfunction "3_P$2") (pintype "passive"))
      (node (ref "J13") (pin "P$3") (pinfunction "1_P$3") (pintype "passive"))
      (node (ref "J14") (pin "P$2") (pinfunction "3_P$2") (pintype "passive"))
      (node (ref "J14") (pin "P$3") (pinfunction "1_P$3") (pintype "passive"))
      (node (ref "J2") (pin "P$3") (pinfunction "1_P$3") (pintype "passive"))
      (node (ref "J3") (pin "P$3") (pinfunction "1_P$3") (pintype "passive"))
      (node (ref "J4") (pin "P$3") (pinfunction "1_P$3") (pintype "passive"))
      (node (ref "J5") (pin "P$3") (pinfunction "1_P$3") (pintype "passive"))
      (node (ref "J6") (pin "P$3") (pinfunction "1_P$3") (pintype "passive"))
      (node (ref "J7") (pin "P$2") (pinfunction "3_P$2") (pintype "passive"))
      (node (ref "J7") (pin "P$3") (pinfunction "1_P$3") (pintype "passive"))
      (node (ref "J8") (pin "P$2") (pinfunction "3_P$2") (pintype "passive"))
      (node (ref "J8") (pin "P$3") (pinfunction "1_P$3") (pintype "passive"))
      (node (ref "J9") (pin "P$2") (pinfunction "3_P$2") (pintype "passive"))
      (node (ref "J9") (pin "P$3") (pinfunction "1_P$3") (pintype "passive"))
      (node (ref "OLED1") (pin "GND") (pinfunction "GND_GND") (pintype "bidirectional"))
      (node (ref "R1") (pin "1") (pinfunction "1_1") (pintype "passive"))
      (node (ref "R3") (pin "1") (pinfunction "1_1") (pintype "passive"))
      (node (ref "SW1") (pin "C") (pinfunction "C_C") (pintype "passive"))
      (node (ref "SW1") (pin "P2") (pinfunction "2_P2") (pintype "passive"))
    )
    (net (code "17") (name "Net-(CTRL1-3)") (class "Default")
      (node (ref "CTRL1") (pin "1") (pinfunction "3_1") (pintype "passive"))
      (node (ref "J13") (pin "P$1") (pinfunction "2_P$1") (pintype "passive"))
    )
    (net (code "18") (name "Net-(CTRL2-3)") (class "Default")
      (node (ref "CTRL2") (pin "1") (pinfunction "3_1") (pintype "passive"))
      (node (ref "J14") (pin "P$1") (pinfunction "2_P$1") (pintype "passive"))
    )
    (net (code "19") (name "Net-(ENC1-3)") (class "Default")
      (node (ref "ENC1") (pin "1") (pinfunction "3_1") (pintype "passive"))
      (node (ref "SW1") (pin "B") (pinfunction "B_B") (pintype "passive"))
    )
    (net (code "20") (name "Net-(ENC2-3)") (class "Default")
      (node (ref "ENC2") (pin "1") (pinfunction "3_1") (pintype "passive"))
      (node (ref "SW1") (pin "A") (pinfunction "A_A") (pintype "passive"))
    )
    (net (code "21") (name "Net-(ENCBT-3)") (class "Default")
      (node (ref "ENCBT") (pin "1") (pinfunction "3_1") (pintype "passive"))
      (node (ref "SW1") (pin "P1") (pinfunction "1_P1") (pintype "passive"))
    )
    (net (code "22") (name "Net-(IC2-R_EXT)") (class "Default")
      (node (ref "IC2") (pin "2") (pinfunction "R_EXT_2") (pintype "input"))
      (node (ref "R3") (pin "2") (pinfunction "2_2") (pintype "passive"))
    )
    (net (code "23") (name "Net-(IC2-SDB)") (class "Default")
      (node (ref "IC2") (pin "10") (pinfunction "SDB_10") (pintype "input"))
      (node (ref "R1") (pin "2") (pinfunction "2_2") (pintype "passive"))
      (node (ref "SDB") (pin "1") (pinfunction "3_1") (pintype "passive"))
    )
    (net (code "24") (name "Net-(IN1-3)") (class "Default")
      (node (ref "IN1") (pin "1") (pinfunction "3_1") (pintype "passive"))
      (node (ref "J7") (pin "P$1") (pinfunction "2_P$1") (pintype "passive"))
    )
    (net (code "25") (name "Net-(IN2-3)") (class "Default")
      (node (ref "IN2") (pin "1") (pinfunction "3_1") (pintype "passive"))
      (node (ref "J8") (pin "P$1") (pinfunction "2_P$1") (pintype "passive"))
    )
    (net (code "26") (name "Net-(IN3-3)") (class "Default")
      (node (ref "IN3") (pin "1") (pinfunction "3_1") (pintype "passive"))
      (node (ref "J9") (pin "P$1") (pinfunction "2_P$1") (pintype "passive"))
    )
    (net (code "27") (name "Net-(IN4-3)") (class "Default")
      (node (ref "IN4") (pin "1") (pinfunction "3_1") (pintype "passive"))
      (node (ref "J10") (pin "P$1") (pinfunction "2_P$1") (pintype "passive"))
    )
    (net (code "28") (name "Net-(IN5-3)") (class "Default")
      (node (ref "IN5") (pin "1") (pinfunction "3_1") (pintype "passive"))
      (node (ref "J11") (pin "P$1") (pinfunction "2_P$1") (pintype "passive"))
    )
    (net (code "29") (name "Net-(IN6-3)") (class "Default")
      (node (ref "IN6") (pin "1") (pinfunction "3_1") (pintype "passive"))
      (node (ref "J12") (pin "P$1") (pinfunction "2_P$1") (pintype "passive"))
    )
    (net (code "30") (name "Net-(J1-2)") (class "Default")
      (node (ref "J1") (pin "P$1") (pinfunction "2_P$1") (pintype "passive"))
      (node (ref "OUT1") (pin "1") (pinfunction "3_1") (pintype "passive"))
    )
    (net (code "31") (name "Net-(J2-2)") (class "Default")
      (node (ref "J2") (pin "P$1") (pinfunction "2_P$1") (pintype "passive"))
      (node (ref "OUT2") (pin "1") (pinfunction "3_1") (pintype "passive"))
    )
    (net (code "32") (name "Net-(J3-2)") (class "Default")
      (node (ref "J3") (pin "P$1") (pinfunction "2_P$1") (pintype "passive"))
      (node (ref "OUT3") (pin "1") (pinfunction "3_1") (pintype "passive"))
    )
    (net (code "33") (name "Net-(J4-2)") (class "Default")
      (node (ref "J4") (pin "P$1") (pinfunction "2_P$1") (pintype "passive"))
      (node (ref "OUT4") (pin "1") (pinfunction "3_1") (pintype "passive"))
    )
    (net (code "34") (name "Net-(J5-2)") (class "Default")
      (node (ref "J5") (pin "P$1") (pinfunction "2_P$1") (pintype "passive"))
      (node (ref "OUT5") (pin "1") (pinfunction "3_1") (pintype "passive"))
    )
    (net (code "35") (name "Net-(J6-2)") (class "Default")
      (node (ref "J6") (pin "P$1") (pinfunction "2_P$1") (pintype "passive"))
      (node (ref "OUT6") (pin "1") (pinfunction "3_1") (pintype "passive"))
    )
    (net (code "36") (name "Net-(S1-P)") (class "Default")
      (node (ref "D1") (pin "A") (pinfunction "A_A") (pintype "passive"))
      (node (ref "S1") (pin "3") (pinfunction "P_3") (pintype "passive"))
    )
    (net (code "37") (name "Net-(S1-S)") (class "Default")
      (node (ref "S1") (pin "1") (pinfunction "S_1") (pintype "passive"))
      (node (ref "S2") (pin "1") (pinfunction "S_1") (pintype "passive"))
      (node (ref "S3") (pin "1") (pinfunction "S_1") (pintype "passive"))
      (node (ref "S4") (pin "1") (pinfunction "S_1") (pintype "passive"))
      (node (ref "S5") (pin "1") (pinfunction "S_1") (pintype "passive"))
      (node (ref "S6") (pin "1") (pinfunction "S_1") (pintype "passive"))
      (node (ref "SWA1") (pin "1") (pinfunction "3_1") (pintype "passive"))
    )
    (net (code "38") (name "Net-(S2-P)") (class "Default")
      (node (ref "D2") (pin "A") (pinfunction "A_A") (pintype "passive"))
      (node (ref "S2") (pin "3") (pinfunction "P_3") (pintype "passive"))
    )
    (net (code "39") (name "Net-(S3-P)") (class "Default")
      (node (ref "D3") (pin "A") (pinfunction "A_A") (pintype "passive"))
      (node (ref "S3") (pin "3") (pinfunction "P_3") (pintype "passive"))
    )
    (net (code "40") (name "Net-(S4-P)") (class "Default")
      (node (ref "D4") (pin "A") (pinfunction "A_A") (pintype "passive"))
      (node (ref "S4") (pin "3") (pinfunction "P_3") (pintype "passive"))
    )
    (net (code "41") (name "Net-(S5-P)") (class "Default")
      (node (ref "D5") (pin "A") (pinfunction "A_A") (pintype "passive"))
      (node (ref "S5") (pin "3") (pinfunction "P_3") (pintype "passive"))
    )
    (net (code "42") (name "Net-(S6-P)") (class "Default")
      (node (ref "D6") (pin "A") (pinfunction "A_A") (pintype "passive"))
      (node (ref "S6") (pin "3") (pinfunction "P_3") (pintype "passive"))
    )
    (net (code "43") (name "Net-(S7-P)") (class "Default")
      (node (ref "D7") (pin "A") (pinfunction "A_A") (pintype "passive"))
      (node (ref "S7") (pin "3") (pinfunction "P_3") (pintype "passive"))
    )
    (net (code "44") (name "Net-(S8-P)") (class "Default")
      (node (ref "D8") (pin "A") (pinfunction "A_A") (pintype "passive"))
      (node (ref "S8") (pin "3") (pinfunction "P_3") (pintype "passive"))
    )
    (net (code "45") (name "Net-(S9-P)") (class "Default")
      (node (ref "D9") (pin "A") (pinfunction "A_A") (pintype "passive"))
      (node (ref "S9") (pin "3") (pinfunction "P_3") (pintype "passive"))
    )
    (net (code "46") (name "Net-(S10-P)") (class "Default")
      (node (ref "D10") (pin "A") (pinfunction "A_A") (pintype "passive"))
      (node (ref "S10") (pin "3") (pinfunction "P_3") (pintype "passive"))
    )
    (net (code "47") (name "Net-(S10-S)") (class "Default")
      (node (ref "S10") (pin "1") (pinfunction "S_1") (pintype "passive"))
      (node (ref "S11") (pin "1") (pinfunction "S_1") (pintype "passive"))
      (node (ref "S12") (pin "1") (pinfunction "S_1") (pintype "passive"))
      (node (ref "S7") (pin "1") (pinfunction "S_1") (pintype "passive"))
      (node (ref "S8") (pin "1") (pinfunction "S_1") (pintype "passive"))
      (node (ref "S9") (pin "1") (pinfunction "S_1") (pintype "passive"))
      (node (ref "SWA2") (pin "1") (pinfunction "3_1") (pintype "passive"))
    )
    (net (code "48") (name "Net-(S11-P)") (class "Default")
      (node (ref "D11") (pin "A") (pinfunction "A_A") (pintype "passive"))
      (node (ref "S11") (pin "3") (pinfunction "P_3") (pintype "passive"))
    )
    (net (code "49") (name "Net-(S12-P)") (class "Default")
      (node (ref "D12") (pin "A") (pinfunction "A_A") (pintype "passive"))
      (node (ref "S12") (pin "3") (pinfunction "P_3") (pintype "passive"))
    )
    (net (code "50") (name "Net-(S13-P)") (class "Default")
      (node (ref "D13") (pin "A") (pinfunction "A_A") (pintype "passive"))
      (node (ref "S13") (pin "3") (pinfunction "P_3") (pintype "passive"))
    )
    (net (code "51") (name "Net-(S13-S)") (class "Default")
      (node (ref "S13") (pin "1") (pinfunction "S_1") (pintype "passive"))
      (node (ref "S14") (pin "1") (pinfunction "S_1") (pintype "passive"))
      (node (ref "S15") (pin "1") (pinfunction "S_1") (pintype "passive"))
      (node (ref "S16") (pin "1") (pinfunction "S_1") (pintype "passive"))
      (node (ref "S17") (pin "1") (pinfunction "S_1") (pintype "passive"))
      (node (ref "S18") (pin "1") (pinfunction "S_1") (pintype "passive"))
      (node (ref "SWA3") (pin "1") (pinfunction "3_1") (pintype "passive"))
    )
    (net (code "52") (name "Net-(S14-P)") (class "Default")
      (node (ref "D14") (pin "A") (pinfunction "A_A") (pintype "passive"))
      (node (ref "S14") (pin "3") (pinfunction "P_3") (pintype "passive"))
    )
    (net (code "53") (name "Net-(S15-P)") (class "Default")
      (node (ref "D15") (pin "A") (pinfunction "A_A") (pintype "passive"))
      (node (ref "S15") (pin "3") (pinfunction "P_3") (pintype "passive"))
    )
    (net (code "54") (name "Net-(S16-P)") (class "Default")
      (node (ref "D16") (pin "A") (pinfunction "A_A") (pintype "passive"))
      (node (ref "S16") (pin "3") (pinfunction "P_3") (pintype "passive"))
    )
    (net (code "55") (name "Net-(S17-P)") (class "Default")
      (node (ref "D17") (pin "A") (pinfunction "A_A") (pintype "passive"))
      (node (ref "S17") (pin "3") (pinfunction "P_3") (pintype "passive"))
    )
    (net (code "56") (name "Net-(S18-P)") (class "Default")
      (node (ref "D18") (pin "A") (pinfunction "A_A") (pintype "passive"))
      (node (ref "S18") (pin "3") (pinfunction "P_3") (pintype "passive"))
    )
    (net (code "57") (name "Net-(S19-P)") (class "Default")
      (node (ref "D19") (pin "A") (pinfunction "A_A") (pintype "passive"))
      (node (ref "S19") (pin "3") (pinfunction "P_3") (pintype "passive"))
    )
    (net (code "58") (name "Net-(S19-S)") (class "Default")
      (node (ref "S19") (pin "1") (pinfunction "S_1") (pintype "passive"))
      (node (ref "S20") (pin "1") (pinfunction "S_1") (pintype "passive"))
      (node (ref "S21") (pin "1") (pinfunction "S_1") (pintype "passive"))
      (node (ref "S22") (pin "1") (pinfunction "S_1") (pintype "passive"))
      (node (ref "S23") (pin "1") (pinfunction "S_1") (pintype "passive"))
      (node (ref "S24") (pin "1") (pinfunction "S_1") (pintype "passive"))
      (node (ref "SWA4") (pin "1") (pinfunction "3_1") (pintype "passive"))
    )
    (net (code "59") (name "Net-(S20-P)") (class "Default")
      (node (ref "D20") (pin "A") (pinfunction "A_A") (pintype "passive"))
      (node (ref "S20") (pin "3") (pinfunction "P_3") (pintype "passive"))
    )
    (net (code "60") (name "Net-(S21-P)") (class "Default")
      (node (ref "D21") (pin "A") (pinfunction "A_A") (pintype "passive"))
      (node (ref "S21") (pin "3") (pinfunction "P_3") (pintype "passive"))
    )
    (net (code "61") (name "Net-(S22-P)") (class "Default")
      (node (ref "D22") (pin "A") (pinfunction "A_A") (pintype "passive"))
      (node (ref "S22") (pin "3") (pinfunction "P_3") (pintype "passive"))
    )
    (net (code "62") (name "Net-(S23-P)") (class "Default")
      (node (ref "D23") (pin "A") (pinfunction "A_A") (pintype "passive"))
      (node (ref "S23") (pin "3") (pinfunction "P_3") (pintype "passive"))
    )
    (net (code "63") (name "Net-(S24-P)") (class "Default")
      (node (ref "D24") (pin "A") (pinfunction "A_A") (pintype "passive"))
      (node (ref "S24") (pin "3") (pinfunction "P_3") (pintype "passive"))
    )
    (net (code "64") (name "Net-(S25-P)") (class "Default")
      (node (ref "D25") (pin "A") (pinfunction "A_A") (pintype "passive"))
      (node (ref "S25") (pin "3") (pinfunction "P_3") (pintype "passive"))
    )
    (net (code "65") (name "Net-(S25-S)") (class "Default")
      (node (ref "S25") (pin "1") (pinfunction "S_1") (pintype "passive"))
      (node (ref "S26") (pin "1") (pinfunction "S_1") (pintype "passive"))
      (node (ref "S27") (pin "1") (pinfunction "S_1") (pintype "passive"))
      (node (ref "S28") (pin "1") (pinfunction "S_1") (pintype "passive"))
      (node (ref "S29") (pin "1") (pinfunction "S_1") (pintype "passive"))
      (node (ref "S30") (pin "1") (pinfunction "S_1") (pintype "passive"))
      (node (ref "SWA5") (pin "1") (pinfunction "3_1") (pintype "passive"))
    )
    (net (code "66") (name "Net-(S26-P)") (class "Default")
      (node (ref "D26") (pin "A") (pinfunction "A_A") (pintype "passive"))
      (node (ref "S26") (pin "3") (pinfunction "P_3") (pintype "passive"))
    )
    (net (code "67") (name "Net-(S27-P)") (class "Default")
      (node (ref "D27") (pin "A") (pinfunction "A_A") (pintype "passive"))
      (node (ref "S27") (pin "3") (pinfunction "P_3") (pintype "passive"))
    )
    (net (code "68") (name "Net-(S28-P)") (class "Default")
      (node (ref "D28") (pin "A") (pinfunction "A_A") (pintype "passive"))
      (node (ref "S28") (pin "3") (pinfunction "P_3") (pintype "passive"))
    )
    (net (code "69") (name "Net-(S29-P)") (class "Default")
      (node (ref "D29") (pin "A") (pinfunction "A_A") (pintype "passive"))
      (node (ref "S29") (pin "3") (pinfunction "P_3") (pintype "passive"))
    )
    (net (code "70") (name "Net-(S30-P)") (class "Default")
      (node (ref "D30") (pin "A") (pinfunction "A_A") (pintype "passive"))
      (node (ref "S30") (pin "3") (pinfunction "P_3") (pintype "passive"))
    )
    (net (code "71") (name "Net-(S31-P)") (class "Default")
      (node (ref "D31") (pin "A") (pinfunction "A_A") (pintype "passive"))
      (node (ref "S31") (pin "3") (pinfunction "P_3") (pintype "passive"))
    )
    (net (code "72") (name "Net-(S31-S)") (class "Default")
      (node (ref "S31") (pin "1") (pinfunction "S_1") (pintype "passive"))
      (node (ref "S32") (pin "1") (pinfunction "S_1") (pintype "passive"))
      (node (ref "S33") (pin "1") (pinfunction "S_1") (pintype "passive"))
      (node (ref "S34") (pin "1") (pinfunction "S_1") (pintype "passive"))
      (node (ref "S35") (pin "1") (pinfunction "S_1") (pintype "passive"))
      (node (ref "S36") (pin "1") (pinfunction "S_1") (pintype "passive"))
      (node (ref "SWA6") (pin "1") (pinfunction "3_1") (pintype "passive"))
    )
    (net (code "73") (name "Net-(S32-P)") (class "Default")
      (node (ref "D32") (pin "A") (pinfunction "A_A") (pintype "passive"))
      (node (ref "S32") (pin "3") (pinfunction "P_3") (pintype "passive"))
    )
    (net (code "74") (name "Net-(S33-P)") (class "Default")
      (node (ref "D33") (pin "A") (pinfunction "A_A") (pintype "passive"))
      (node (ref "S33") (pin "3") (pinfunction "P_3") (pintype "passive"))
    )
    (net (code "75") (name "Net-(S34-P)") (class "Default")
      (node (ref "D34") (pin "A") (pinfunction "A_A") (pintype "passive"))
      (node (ref "S34") (pin "3") (pinfunction "P_3") (pintype "passive"))
    )
    (net (code "76") (name "Net-(S35-P)") (class "Default")
      (node (ref "D35") (pin "A") (pinfunction "A_A") (pintype "passive"))
      (node (ref "S35") (pin "3") (pinfunction "P_3") (pintype "passive"))
    )
    (net (code "77") (name "Net-(S36-P)") (class "Default")
      (node (ref "D36") (pin "A") (pinfunction "A_A") (pintype "passive"))
      (node (ref "S36") (pin "3") (pinfunction "P_3") (pintype "passive"))
    )
    (net (code "78") (name "Net-(SWC1-3)") (class "Default")
      (node (ref "D1") (pin "C") (pinfunction "C_C") (pintype "passive"))
      (node (ref "D13") (pin "C") (pinfunction "C_C") (pintype "passive"))
      (node (ref "D19") (pin "C") (pinfunction "C_C") (pintype "passive"))
      (node (ref "D25") (pin "C") (pinfunction "C_C") (pintype "passive"))
      (node (ref "D31") (pin "C") (pinfunction "C_C") (pintype "passive"))
      (node (ref "D7") (pin "C") (pinfunction "C_C") (pintype "passive"))
      (node (ref "SWC1") (pin "1") (pinfunction "3_1") (pintype "passive"))
    )
    (net (code "79") (name "Net-(SWC2-3)") (class "Default")
      (node (ref "D14") (pin "C") (pinfunction "C_C") (pintype "passive"))
      (node (ref "D2") (pin "C") (pinfunction "C_C") (pintype "passive"))
      (node (ref "D20") (pin "C") (pinfunction "C_C") (pintype "passive"))
      (node (ref "D26") (pin "C") (pinfunction "C_C") (pintype "passive"))
      (node (ref "D32") (pin "C") (pinfunction "C_C") (pintype "passive"))
      (node (ref "D8") (pin "C") (pinfunction "C_C") (pintype "passive"))
      (node (ref "SWC2") (pin "1") (pinfunction "3_1") (pintype "passive"))
    )
    (net (code "80") (name "Net-(SWC3-3)") (class "Default")
      (node (ref "D15") (pin "C") (pinfunction "C_C") (pintype "passive"))
      (node (ref "D21") (pin "C") (pinfunction "C_C") (pintype "passive"))
      (node (ref "D27") (pin "C") (pinfunction "C_C") (pintype "passive"))
      (node (ref "D3") (pin "C") (pinfunction "C_C") (pintype "passive"))
      (node (ref "D33") (pin "C") (pinfunction "C_C") (pintype "passive"))
      (node (ref "D9") (pin "C") (pinfunction "C_C") (pintype "passive"))
      (node (ref "SWC3") (pin "1") (pinfunction "3_1") (pintype "passive"))
    )
    (net (code "81") (name "Net-(SWC4-3)") (class "Default")
      (node (ref "D10") (pin "C") (pinfunction "C_C") (pintype "passive"))
      (node (ref "D16") (pin "C") (pinfunction "C_C") (pintype "passive"))
      (node (ref "D22") (pin "C") (pinfunction "C_C") (pintype "passive"))
      (node (ref "D28") (pin "C") (pinfunction "C_C") (pintype "passive"))
      (node (ref "D34") (pin "C") (pinfunction "C_C") (pintype "passive"))
      (node (ref "D4") (pin "C") (pinfunction "C_C") (pintype "passive"))
      (node (ref "SWC4") (pin "1") (pinfunction "3_1") (pintype "passive"))
    )
    (net (code "82") (name "Net-(SWC5-3)") (class "Default")
      (node (ref "D11") (pin "C") (pinfunction "C_C") (pintype "passive"))
      (node (ref "D17") (pin "C") (pinfunction "C_C") (pintype "passive"))
      (node (ref "D23") (pin "C") (pinfunction "C_C") (pintype "passive"))
      (node (ref "D29") (pin "C") (pinfunction "C_C") (pintype "passive"))
      (node (ref "D35") (pin "C") (pinfunction "C_C") (pintype "passive"))
      (node (ref "D5") (pin "C") (pinfunction "C_C") (pintype "passive"))
      (node (ref "SWC5") (pin "1") (pinfunction "3_1") (pintype "passive"))
    )
    (net (code "83") (name "Net-(SWC6-3)") (class "Default")
      (node (ref "D12") (pin "C") (pinfunction "C_C") (pintype "passive"))
      (node (ref "D18") (pin "C") (pinfunction "C_C") (pintype "passive"))
      (node (ref "D24") (pin "C") (pinfunction "C_C") (pintype "passive"))
      (node (ref "D30") (pin "C") (pinfunction "C_C") (pintype "passive"))
      (node (ref "D36") (pin "C") (pinfunction "C_C") (pintype "passive"))
      (node (ref "D6") (pin "C") (pinfunction "C_C") (pintype "passive"))
      (node (ref "SWC6") (pin "1") (pinfunction "3_1") (pintype "passive"))
    )
    (net (code "84") (name "unconnected-(IC2-CS7-Pad28)") (class "Default")
      (node (ref "IC2") (pin "28") (pinfunction "CS7_28") (pintype "output"))
    )
    (net (code "85") (name "unconnected-(IC2-CS8-Pad1)") (class "Default")
      (node (ref "IC2") (pin "1") (pinfunction "CS8_1") (pintype "output"))
    )
    (net (code "86") (name "unconnected-(IC2-INTB-Pad9)") (class "Default")
      (node (ref "IC2") (pin "9") (pinfunction "INTB_9") (pintype "input"))
    )
    (net (code "87") (name "unconnected-(IC2-SYNC-Pad5)") (class "Default")
      (node (ref "IC2") (pin "5") (pinfunction "SYNC_5") (pintype "input"))
    )
    (net (code "88") (name "unconnected-(J1-3-PadP$2)") (class "Default")
      (node (ref "J1") (pin "P$2") (pinfunction "3_P$2") (pintype "passive"))
    )
    (net (code "89") (name "unconnected-(J2-3-PadP$2)") (class "Default")
      (node (ref "J2") (pin "P$2") (pinfunction "3_P$2") (pintype "passive"))
    )
    (net (code "90") (name "unconnected-(J3-3-PadP$2)") (class "Default")
      (node (ref "J3") (pin "P$2") (pinfunction "3_P$2") (pintype "passive"))
    )
    (net (code "91") (name "unconnected-(J4-3-PadP$2)") (class "Default")
      (node (ref "J4") (pin "P$2") (pinfunction "3_P$2") (pintype "passive"))
    )
    (net (code "92") (name "unconnected-(J5-3-PadP$2)") (class "Default")
      (node (ref "J5") (pin "P$2") (pinfunction "3_P$2") (pintype "passive"))
    )
    (net (code "93") (name "unconnected-(J6-3-PadP$2)") (class "Default")
      (node (ref "J6") (pin "P$2") (pinfunction "3_P$2") (pintype "passive"))
    )
    (net (code "94") (name "unconnected-(NA1-3-Pad1)") (class "Default")
      (node (ref "NA1") (pin "1") (pinfunction "3_1") (pintype "passive"))
    )
    (net (code "95") (name "unconnected-(NA2-3-Pad1)") (class "Default")
      (node (ref "NA2") (pin "1") (pinfunction "3_1") (pintype "passive"))
    )
    (net (code "96") (name "unconnected-(S1-P1-Pad4)") (class "Default")
      (node (ref "S1") (pin "4") (pinfunction "P1_4") (pintype "passive"))
    )
    (net (code "97") (name "unconnected-(S1-S1-Pad2)") (class "Default")
      (node (ref "S1") (pin "2") (pinfunction "S1_2") (pintype "passive"))
    )
    (net (code "98") (name "unconnected-(S2-P1-Pad4)") (class "Default")
      (node (ref "S2") (pin "4") (pinfunction "P1_4") (pintype "passive"))
    )
    (net (code "99") (name "unconnected-(S2-S1-Pad2)") (class "Default")
      (node (ref "S2") (pin "2") (pinfunction "S1_2") (pintype "passive"))
    )
    (net (code "100") (name "unconnected-(S3-P1-Pad4)") (class "Default")
      (node (ref "S3") (pin "4") (pinfunction "P1_4") (pintype "passive"))
    )
    (net (code "101") (name "unconnected-(S3-S1-Pad2)") (class "Default")
      (node (ref "S3") (pin "2") (pinfunction "S1_2") (pintype "passive"))
    )
    (net (code "102") (name "unconnected-(S4-P1-Pad4)") (class "Default")
      (node (ref "S4") (pin "4") (pinfunction "P1_4") (pintype "passive"))
    )
    (net (code "103") (name "unconnected-(S4-S1-Pad2)") (class "Default")
      (node (ref "S4") (pin "2") (pinfunction "S1_2") (pintype "passive"))
    )
    (net (code "104") (name "unconnected-(S5-P1-Pad4)") (class "Default")
      (node (ref "S5") (pin "4") (pinfunction "P1_4") (pintype "passive"))
    )
    (net (code "105") (name "unconnected-(S5-S1-Pad2)") (class "Default")
      (node (ref "S5") (pin "2") (pinfunction "S1_2") (pintype "passive"))
    )
    (net (code "106") (name "unconnected-(S6-P1-Pad4)") (class "Default")
      (node (ref "S6") (pin "4") (pinfunction "P1_4") (pintype "passive"))
    )
    (net (code "107") (name "unconnected-(S6-S1-Pad2)") (class "Default")
      (node (ref "S6") (pin "2") (pinfunction "S1_2") (pintype "passive"))
    )
    (net (code "108") (name "unconnected-(S7-P1-Pad4)") (class "Default")
      (node (ref "S7") (pin "4") (pinfunction "P1_4") (pintype "passive"))
    )
    (net (code "109") (name "unconnected-(S7-S1-Pad2)") (class "Default")
      (node (ref "S7") (pin "2") (pinfunction "S1_2") (pintype "passive"))
    )
    (net (code "110") (name "unconnected-(S8-P1-Pad4)") (class "Default")
      (node (ref "S8") (pin "4") (pinfunction "P1_4") (pintype "passive"))
    )
    (net (code "111") (name "unconnected-(S8-S1-Pad2)") (class "Default")
      (node (ref "S8") (pin "2") (pinfunction "S1_2") (pintype "passive"))
    )
    (net (code "112") (name "unconnected-(S9-P1-Pad4)") (class "Default")
      (node (ref "S9") (pin "4") (pinfunction "P1_4") (pintype "passive"))
    )
    (net (code "113") (name "unconnected-(S9-S1-Pad2)") (class "Default")
      (node (ref "S9") (pin "2") (pinfunction "S1_2") (pintype "passive"))
    )
    (net (code "114") (name "unconnected-(S10-P1-Pad4)") (class "Default")
      (node (ref "S10") (pin "4") (pinfunction "P1_4") (pintype "passive"))
    )
    (net (code "115") (name "unconnected-(S10-S1-Pad2)") (class "Default")
      (node (ref "S10") (pin "2") (pinfunction "S1_2") (pintype "passive"))
    )
    (net (code "116") (name "unconnected-(S11-P1-Pad4)") (class "Default")
      (node (ref "S11") (pin "4") (pinfunction "P1_4") (pintype "passive"))
    )
    (net (code "117") (name "unconnected-(S11-S1-Pad2)") (class "Default")
      (node (ref "S11") (pin "2") (pinfunction "S1_2") (pintype "passive"))
    )
    (net (code "118") (name "unconnected-(S12-P1-Pad4)") (class "Default")
      (node (ref "S12") (pin "4") (pinfunction "P1_4") (pintype "passive"))
    )
    (net (code "119") (name "unconnected-(S12-S1-Pad2)") (class "Default")
      (node (ref "S12") (pin "2") (pinfunction "S1_2") (pintype "passive"))
    )
    (net (code "120") (name "unconnected-(S13-P1-Pad4)") (class "Default")
      (node (ref "S13") (pin "4") (pinfunction "P1_4") (pintype "passive"))
    )
    (net (code "121") (name "unconnected-(S13-S1-Pad2)") (class "Default")
      (node (ref "S13") (pin "2") (pinfunction "S1_2") (pintype "passive"))
    )
    (net (code "122") (name "unconnected-(S14-P1-Pad4)") (class "Default")
      (node (ref "S14") (pin "4") (pinfunction "P1_4") (pintype "passive"))
    )
    (net (code "123") (name "unconnected-(S14-S1-Pad2)") (class "Default")
      (node (ref "S14") (pin "2") (pinfunction "S1_2") (pintype "passive"))
    )
    (net (code "124") (name "unconnected-(S15-P1-Pad4)") (class "Default")
      (node (ref "S15") (pin "4") (pinfunction "P1_4") (pintype "passive"))
    )
    (net (code "125") (name "unconnected-(S15-S1-Pad2)") (class "Default")
      (node (ref "S15") (pin "2") (pinfunction "S1_2") (pintype "passive"))
    )
    (net (code "126") (name "unconnected-(S16-P1-Pad4)") (class "Default")
      (node (ref "S16") (pin "4") (pinfunction "P1_4") (pintype "passive"))
    )
    (net (code "127") (name "unconnected-(S16-S1-Pad2)") (class "Default")
      (node (ref "S16") (pin "2") (pinfunction "S1_2") (pintype "passive"))
    )
    (net (code "128") (name "unconnected-(S17-P1-Pad4)") (class "Default")
      (node (ref "S17") (pin "4") (pinfunction "P1_4") (pintype "passive"))
    )
    (net (code "129") (name "unconnected-(S17-S1-Pad2)") (class "Default")
      (node (ref "S17") (pin "2") (pinfunction "S1_2") (pintype "passive"))
    )
    (net (code "130") (name "unconnected-(S18-P1-Pad4)") (class "Default")
      (node (ref "S18") (pin "4") (pinfunction "P1_4") (pintype "passive"))
    )
    (net (code "131") (name "unconnected-(S18-S1-Pad2)") (class "Default")
      (node (ref "S18") (pin "2") (pinfunction "S1_2") (pintype "passive"))
    )
    (net (code "132") (name "unconnected-(S19-P1-Pad4)") (class "Default")
      (node (ref "S19") (pin "4") (pinfunction "P1_4") (pintype "passive"))
    )
    (net (code "133") (name "unconnected-(S19-S1-Pad2)") (class "Default")
      (node (ref "S19") (pin "2") (pinfunction "S1_2") (pintype "passive"))
    )
    (net (code "134") (name "unconnected-(S20-P1-Pad4)") (class "Default")
      (node (ref "S20") (pin "4") (pinfunction "P1_4") (pintype "passive"))
    )
    (net (code "135") (name "unconnected-(S20-S1-Pad2)") (class "Default")
      (node (ref "S20") (pin "2") (pinfunction "S1_2") (pintype "passive"))
    )
    (net (code "136") (name "unconnected-(S21-P1-Pad4)") (class "Default")
      (node (ref "S21") (pin "4") (pinfunction "P1_4") (pintype "passive"))
    )
    (net (code "137") (name "unconnected-(S21-S1-Pad2)") (class "Default")
      (node (ref "S21") (pin "2") (pinfunction "S1_2") (pintype "passive"))
    )
    (net (code "138") (name "unconnected-(S22-P1-Pad4)") (class "Default")
      (node (ref "S22") (pin "4") (pinfunction "P1_4") (pintype "passive"))
    )
    (net (code "139") (name "unconnected-(S22-S1-Pad2)") (class "Default")
      (node (ref "S22") (pin "2") (pinfunction "S1_2") (pintype "passive"))
    )
    (net (code "140") (name "unconnected-(S23-P1-Pad4)") (class "Default")
      (node (ref "S23") (pin "4") (pinfunction "P1_4") (pintype "passive"))
    )
    (net (code "141") (name "unconnected-(S23-S1-Pad2)") (class "Default")
      (node (ref "S23") (pin "2") (pinfunction "S1_2") (pintype "passive"))
    )
    (net (code "142") (name "unconnected-(S24-P1-Pad4)") (class "Default")
      (node (ref "S24") (pin "4") (pinfunction "P1_4") (pintype "passive"))
    )
    (net (code "143") (name "unconnected-(S24-S1-Pad2)") (class "Default")
      (node (ref "S24") (pin "2") (pinfunction "S1_2") (pintype "passive"))
    )
    (net (code "144") (name "unconnected-(S25-P1-Pad4)") (class "Default")
      (node (ref "S25") (pin "4") (pinfunction "P1_4") (pintype "passive"))
    )
    (net (code "145") (name "unconnected-(S25-S1-Pad2)") (class "Default")
      (node (ref "S25") (pin "2") (pinfunction "S1_2") (pintype "passive"))
    )
    (net (code "146") (name "unconnected-(S26-P1-Pad4)") (class "Default")
      (node (ref "S26") (pin "4") (pinfunction "P1_4") (pintype "passive"))
    )
    (net (code "147") (name "unconnected-(S26-S1-Pad2)") (class "Default")
      (node (ref "S26") (pin "2") (pinfunction "S1_2") (pintype "passive"))
    )
    (net (code "148") (name "unconnected-(S27-P1-Pad4)") (class "Default")
      (node (ref "S27") (pin "4") (pinfunction "P1_4") (pintype "passive"))
    )
    (net (code "149") (name "unconnected-(S27-S1-Pad2)") (class "Default")
      (node (ref "S27") (pin "2") (pinfunction "S1_2") (pintype "passive"))
    )
    (net (code "150") (name "unconnected-(S28-P1-Pad4)") (class "Default")
      (node (ref "S28") (pin "4") (pinfunction "P1_4") (pintype "passive"))
    )
    (net (code "151") (name "unconnected-(S28-S1-Pad2)") (class "Default")
      (node (ref "S28") (pin "2") (pinfunction "S1_2") (pintype "passive"))
    )
    (net (code "152") (name "unconnected-(S29-P1-Pad4)") (class "Default")
      (node (ref "S29") (pin "4") (pinfunction "P1_4") (pintype "passive"))
    )
    (net (code "153") (name "unconnected-(S29-S1-Pad2)") (class "Default")
      (node (ref "S29") (pin "2") (pinfunction "S1_2") (pintype "passive"))
    )
    (net (code "154") (name "unconnected-(S30-P1-Pad4)") (class "Default")
      (node (ref "S30") (pin "4") (pinfunction "P1_4") (pintype "passive"))
    )
    (net (code "155") (name "unconnected-(S30-S1-Pad2)") (class "Default")
      (node (ref "S30") (pin "2") (pinfunction "S1_2") (pintype "passive"))
    )
    (net (code "156") (name "unconnected-(S31-P1-Pad4)") (class "Default")
      (node (ref "S31") (pin "4") (pinfunction "P1_4") (pintype "passive"))
    )
    (net (code "157") (name "unconnected-(S31-S1-Pad2)") (class "Default")
      (node (ref "S31") (pin "2") (pinfunction "S1_2") (pintype "passive"))
    )
    (net (code "158") (name "unconnected-(S32-P1-Pad4)") (class "Default")
      (node (ref "S32") (pin "4") (pinfunction "P1_4") (pintype "passive"))
    )
    (net (code "159") (name "unconnected-(S32-S1-Pad2)") (class "Default")
      (node (ref "S32") (pin "2") (pinfunction "S1_2") (pintype "passive"))
    )
    (net (code "160") (name "unconnected-(S33-P1-Pad4)") (class "Default")
      (node (ref "S33") (pin "4") (pinfunction "P1_4") (pintype "passive"))
    )
    (net (code "161") (name "unconnected-(S33-S1-Pad2)") (class "Default")
      (node (ref "S33") (pin "2") (pinfunction "S1_2") (pintype "passive"))
    )
    (net (code "162") (name "unconnected-(S34-P1-Pad4)") (class "Default")
      (node (ref "S34") (pin "4") (pinfunction "P1_4") (pintype "passive"))
    )
    (net (code "163") (name "unconnected-(S34-S1-Pad2)") (class "Default")
      (node (ref "S34") (pin "2") (pinfunction "S1_2") (pintype "passive"))
    )
    (net (code "164") (name "unconnected-(S35-P1-Pad4)") (class "Default")
      (node (ref "S35") (pin "4") (pinfunction "P1_4") (pintype "passive"))
    )
    (net (code "165") (name "unconnected-(S35-S1-Pad2)") (class "Default")
      (node (ref "S35") (pin "2") (pinfunction "S1_2") (pintype "passive"))
    )
    (net (code "166") (name "unconnected-(S36-P1-Pad4)") (class "Default")
      (node (ref "S36") (pin "4") (pinfunction "P1_4") (pintype "passive"))
    )
    (net (code "167") (name "unconnected-(S36-S1-Pad2)") (class "Default")
      (node (ref "S36") (pin "2") (pinfunction "S1_2") (pintype "passive"))
    )
  )
)
